# BME280-Breakout_v13.net
KiCad netlist of a schematic drawn in EAGLE
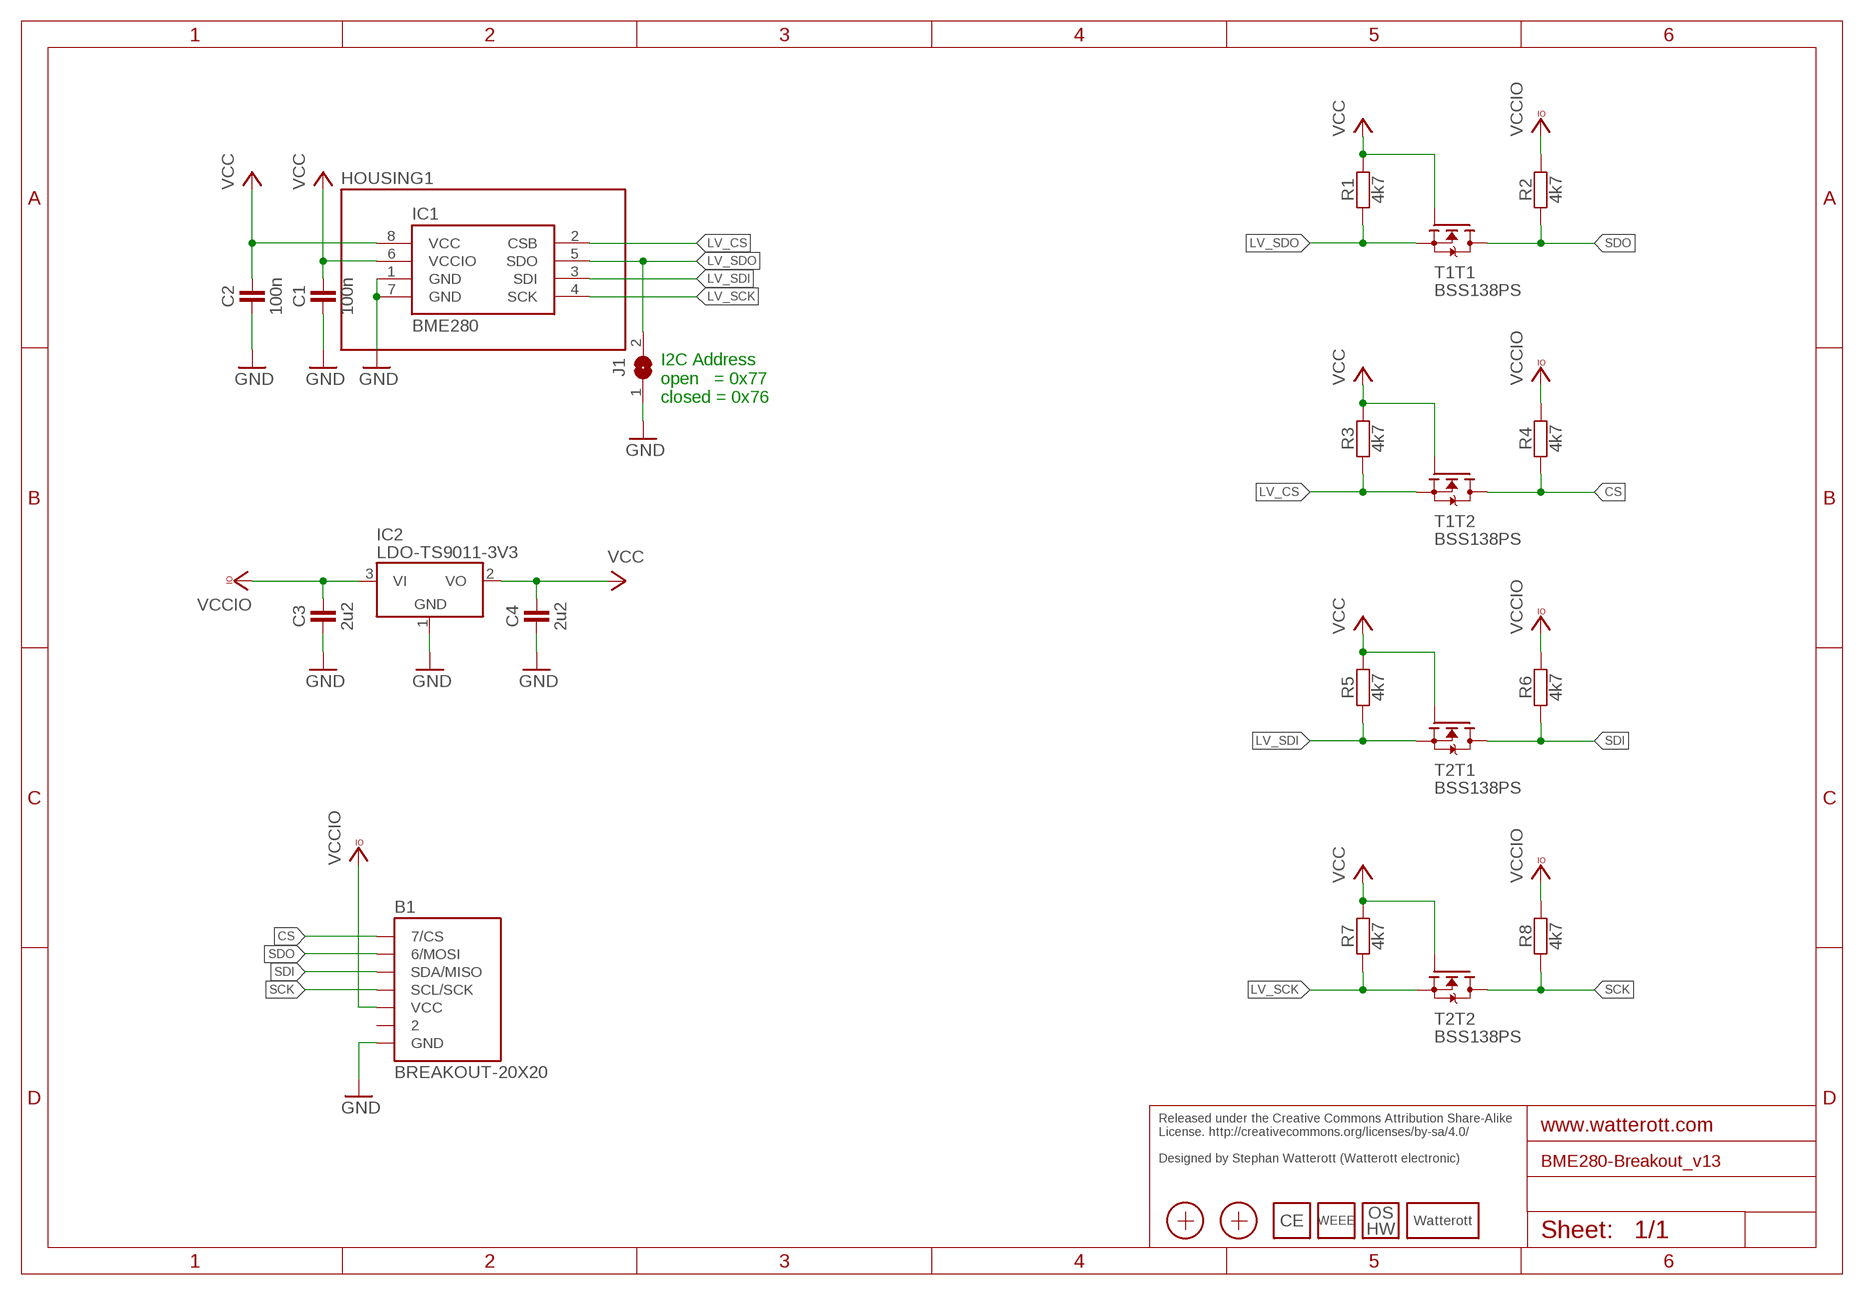
[diagram p0: schematic, sheet 1]

(export (version "E")
  (design (tool "Eeschema 10.0.6"))
  (components
    (comp (ref "B1")
      (value "BREAKOUT-20X20")
      (footprint "eagle-import:BREAKOUT-20X20")
      (libsource (lib "eagle-import") (part "BREAKOUT-20X20"))
    )
    (comp (ref "C1")
      (value "100n")
      (footprint "eagle-import:C0402")
      (libsource (lib "eagle-import") (part "CAPACITOR-0402"))
    )
    (comp (ref "C2")
      (value "100n")
      (footprint "eagle-import:C0402")
      (libsource (lib "eagle-import") (part "CAPACITOR-0402"))
    )
    (comp (ref "C3")
      (value "2u2")
      (footprint "eagle-import:C0402")
      (libsource (lib "eagle-import") (part "CAPACITOR-0402"))
    )
    (comp (ref "C4")
      (value "2u2")
      (footprint "eagle-import:C0402")
      (libsource (lib "eagle-import") (part "CAPACITOR-0402"))
    )
    (comp (ref "HOUSING1")
      (value "SF2")
      (footprint "eagle-import:SF2")
      (libsource (lib "eagle-import") (part "SF2"))
    )
    (comp (ref "IC1")
      (value "BME280")
      (footprint "eagle-import:BME280")
      (libsource (lib "eagle-import") (part "BME280"))
    )
    (comp (ref "IC2")
      (value "LDO-TS9011-3V3")
      (footprint "eagle-import:SOT23")
      (libsource (lib "eagle-import") (part "LDO-TS9011-3V3"))
    )
    (comp (ref "J1")
      (value "JUMPER2-0603")
      (footprint "eagle-import:JUMPER2-0603")
      (libsource (lib "eagle-import") (part "JUMPER2-0603"))
    )
    (comp (ref "LOGO3")
      (value "LOGO_CE-2")
      (footprint "eagle-import:CE_2MM")
      (libsource (lib "eagle-import") (part "LOGO_CE-2"))
    )
    (comp (ref "LOGO4")
      (value "LOGO_WEEE-4")
      (footprint "eagle-import:WEEE_4MM")
      (libsource (lib "eagle-import") (part "LOGO_WEEE-4"))
    )
    (comp (ref "LOGO5")
      (value "LOGO_SPARK-2")
      (footprint "eagle-import:SPARK_2MM")
      (libsource (lib "eagle-import") (part "LOGO_SPARK-2"))
    )
    (comp (ref "LOGO6")
      (value "LOGO_OSHW-2")
      (footprint "eagle-import:OSHW_2MM")
      (libsource (lib "eagle-import") (part "LOGO_OSHW-2"))
    )
    (comp (ref "R1")
      (value "4k7")
      (footprint "eagle-import:C0402")
      (libsource (lib "eagle-import") (part "RESISTOR-0402"))
    )
    (comp (ref "R2")
      (value "4k7")
      (footprint "eagle-import:C0402")
      (libsource (lib "eagle-import") (part "RESISTOR-0402"))
    )
    (comp (ref "R3")
      (value "4k7")
      (footprint "eagle-import:C0402")
      (libsource (lib "eagle-import") (part "RESISTOR-0402"))
    )
    (comp (ref "R4")
      (value "4k7")
      (footprint "eagle-import:C0402")
      (libsource (lib "eagle-import") (part "RESISTOR-0402"))
    )
    (comp (ref "R5")
      (value "4k7")
      (footprint "eagle-import:C0402")
      (libsource (lib "eagle-import") (part "RESISTOR-0402"))
    )
    (comp (ref "R6")
      (value "4k7")
      (footprint "eagle-import:C0402")
      (libsource (lib "eagle-import") (part "RESISTOR-0402"))
    )
    (comp (ref "R7")
      (value "4k7")
      (footprint "eagle-import:C0402")
      (libsource (lib "eagle-import") (part "RESISTOR-0402"))
    )
    (comp (ref "R8")
      (value "4k7")
      (footprint "eagle-import:C0402")
      (libsource (lib "eagle-import") (part "RESISTOR-0402"))
    )
    (comp (ref "T1")
      (value "BSS138PS")
      (footprint "eagle-import:SOT363")
      (libsource (lib "eagle-import") (part "BSS138PS"))
    )
    (comp (ref "T2")
      (value "BSS138PS")
      (footprint "eagle-import:SOT363")
      (libsource (lib "eagle-import") (part "BSS138PS"))
    )
    (comp (ref "X1")
      (value "PASSER-07")
      (footprint "eagle-import:PASSER_07MM")
      (libsource (lib "eagle-import") (part "PASSER-07"))
    )
    (comp (ref "X2")
      (value "PASSER-07")
      (footprint "eagle-import:PASSER_07MM")
      (libsource (lib "eagle-import") (part "PASSER-07"))
    )
  )
  (nets
    (net (code "1") (name "CS") (class "Default")
      (node (ref "B1") (pin "CS") (pinfunction "7/CS_CS") (pintype "bidirectional"))
      (node (ref "R4") (pin "1") (pinfunction "1_1") (pintype "passive"))
      (node (ref "T1") (pin "3") (pinfunction "D_3") (pintype "passive"))
    )
    (net (code "2") (name "GND") (class "Default")
      (node (ref "B1") (pin "GND") (pinfunction "GND_GND") (pintype "power_in"))
      (node (ref "C1") (pin "1") (pinfunction "1_1") (pintype "passive"))
      (node (ref "C2") (pin "1") (pinfunction "1_1") (pintype "passive"))
      (node (ref "C3") (pin "1") (pinfunction "1_1") (pintype "passive"))
      (node (ref "C4") (pin "1") (pinfunction "1_1") (pintype "passive"))
      (node (ref "IC1") (pin "1") (pinfunction "GND_1") (pintype "power_in"))
      (node (ref "IC1") (pin "7") (pinfunction "GND_7") (pintype "power_in"))
      (node (ref "IC2") (pin "1") (pinfunction "GND_1") (pintype "passive"))
      (node (ref "J1") (pin "1") (pinfunction "1_1") (pintype "passive"))
    )
    (net (code "3") (name "LV_CS") (class "Default")
      (node (ref "IC1") (pin "2") (pinfunction "CSB_2") (pintype "input"))
      (node (ref "R3") (pin "1") (pinfunction "1_1") (pintype "passive"))
      (node (ref "T1") (pin "4") (pinfunction "S_4") (pintype "passive"))
    )
    (net (code "4") (name "LV_SCK") (class "Default")
      (node (ref "IC1") (pin "4") (pinfunction "SCK_4") (pintype "bidirectional"))
      (node (ref "R7") (pin "1") (pinfunction "1_1") (pintype "passive"))
      (node (ref "T2") (pin "4") (pinfunction "S_4") (pintype "passive"))
    )
    (net (code "5") (name "LV_SDI") (class "Default")
      (node (ref "IC1") (pin "3") (pinfunction "SDI_3") (pintype "bidirectional"))
      (node (ref "R5") (pin "1") (pinfunction "1_1") (pintype "passive"))
      (node (ref "T2") (pin "1") (pinfunction "S_1") (pintype "passive"))
    )
    (net (code "6") (name "LV_SDO") (class "Default")
      (node (ref "IC1") (pin "5") (pinfunction "SDO_5") (pintype "bidirectional"))
      (node (ref "J1") (pin "2") (pinfunction "2_2") (pintype "passive"))
      (node (ref "R1") (pin "1") (pinfunction "1_1") (pintype "passive"))
      (node (ref "T1") (pin "1") (pinfunction "S_1") (pintype "passive"))
    )
    (net (code "7") (name "SCK") (class "Default")
      (node (ref "B1") (pin "SCL/SCK") (pinfunction "SCL/SCK_SCL/SCK") (pintype "bidirectional"))
      (node (ref "R8") (pin "1") (pinfunction "1_1") (pintype "passive"))
      (node (ref "T2") (pin "3") (pinfunction "D_3") (pintype "passive"))
    )
    (net (code "8") (name "SDI") (class "Default")
      (node (ref "B1") (pin "SDA/MISO") (pinfunction "SDA/MISO_SDA/MISO") (pintype "bidirectional"))
      (node (ref "R6") (pin "1") (pinfunction "1_1") (pintype "passive"))
      (node (ref "T2") (pin "6") (pinfunction "D_6") (pintype "passive"))
    )
    (net (code "9") (name "SDO") (class "Default")
      (node (ref "B1") (pin "MOSI") (pinfunction "6/MOSI_MOSI") (pintype "bidirectional"))
      (node (ref "R2") (pin "1") (pinfunction "1_1") (pintype "passive"))
      (node (ref "T1") (pin "6") (pinfunction "D_6") (pintype "passive"))
    )
    (net (code "10") (name "VCC") (class "Default")
      (node (ref "C1") (pin "2") (pinfunction "2_2") (pintype "passive"))
      (node (ref "C2") (pin "2") (pinfunction "2_2") (pintype "passive"))
      (node (ref "C4") (pin "2") (pinfunction "2_2") (pintype "passive"))
      (node (ref "IC1") (pin "6") (pinfunction "VCCIO_6") (pintype "power_in"))
      (node (ref "IC1") (pin "8") (pinfunction "VCC_8") (pintype "power_in"))
      (node (ref "IC2") (pin "2") (pinfunction "VO_2") (pintype "passive"))
      (node (ref "R1") (pin "2") (pinfunction "2_2") (pintype "passive"))
      (node (ref "R3") (pin "2") (pinfunction "2_2") (pintype "passive"))
      (node (ref "R5") (pin "2") (pinfunction "2_2") (pintype "passive"))
      (node (ref "R7") (pin "2") (pinfunction "2_2") (pintype "passive"))
      (node (ref "T1") (pin "2") (pinfunction "G_2") (pintype "passive"))
      (node (ref "T1") (pin "5") (pinfunction "G_5") (pintype "passive"))
      (node (ref "T2") (pin "2") (pinfunction "G_2") (pintype "passive"))
      (node (ref "T2") (pin "5") (pinfunction "G_5") (pintype "passive"))
    )
    (net (code "11") (name "VCCIO") (class "Default")
      (node (ref "B1") (pin "VCC") (pinfunction "VCC_VCC") (pintype "power_in"))
      (node (ref "C3") (pin "2") (pinfunction "2_2") (pintype "passive"))
      (node (ref "IC2") (pin "3") (pinfunction "VI_3") (pintype "input"))
      (node (ref "R2") (pin "2") (pinfunction "2_2") (pintype "passive"))
      (node (ref "R4") (pin "2") (pinfunction "2_2") (pintype "passive"))
      (node (ref "R6") (pin "2") (pinfunction "2_2") (pintype "passive"))
      (node (ref "R8") (pin "2") (pinfunction "2_2") (pintype "passive"))
    )
    (net (code "12") (name "unconnected-(B1-Pad2)") (class "Default")
      (node (ref "B1") (pin "2") (pinfunction "2_2") (pintype "bidirectional"))
    )
  )
)
